# main.net
KiCad netlist of a schematic drawn in Altium Designer
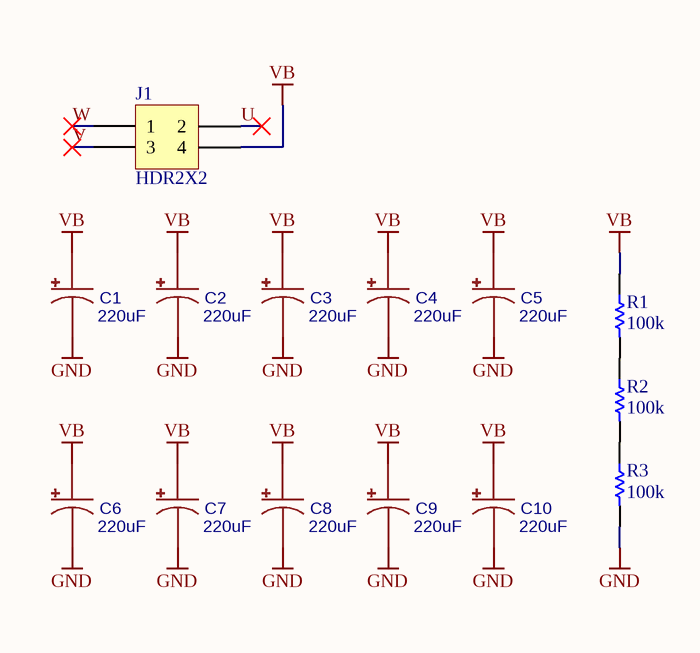
[diagram p0: main.SchDoc]

(export (version "E")
  (design (tool "Eeschema 10.0.6"))
  (components
    (comp (ref "C1")
      (value "220uF")
      (footprint "CAP-TH_BD16.0-P7.50-D1.2-FD")
      (description "UPW2A221MHD")
      (libsource (lib "altium-import") (part "root_0_220uF_"))
    )
    (comp (ref "C2")
      (value "220uF")
      (footprint "CAP-TH_BD16.0-P7.50-D1.2-FD")
      (description "UPW2A221MHD")
      (libsource (lib "altium-import") (part "root_0_220uF_"))
    )
    (comp (ref "C3")
      (value "220uF")
      (footprint "CAP-TH_BD16.0-P7.50-D1.2-FD")
      (description "UPW2A221MHD")
      (libsource (lib "altium-import") (part "root_0_220uF_"))
    )
    (comp (ref "C4")
      (value "220uF")
      (footprint "CAP-TH_BD16.0-P7.50-D1.2-FD")
      (description "UPW2A221MHD")
      (libsource (lib "altium-import") (part "root_0_220uF_"))
    )
    (comp (ref "C5")
      (value "220uF")
      (footprint "CAP-TH_BD16.0-P7.50-D1.2-FD")
      (description "UPW2A221MHD")
      (libsource (lib "altium-import") (part "root_0_220uF_"))
    )
    (comp (ref "C6")
      (value "220uF")
      (footprint "CAP-TH_BD16.0-P7.50-D1.2-FD")
      (description "UPW2A221MHD")
      (libsource (lib "altium-import") (part "root_0_220uF_"))
    )
    (comp (ref "C7")
      (value "220uF")
      (footprint "CAP-TH_BD16.0-P7.50-D1.2-FD")
      (description "UPW2A221MHD")
      (libsource (lib "altium-import") (part "root_0_220uF_"))
    )
    (comp (ref "C8")
      (value "220uF")
      (footprint "CAP-TH_BD16.0-P7.50-D1.2-FD")
      (description "UPW2A221MHD")
      (libsource (lib "altium-import") (part "root_0_220uF_"))
    )
    (comp (ref "C9")
      (value "220uF")
      (footprint "CAP-TH_BD16.0-P7.50-D1.2-FD")
      (description "UPW2A221MHD")
      (libsource (lib "altium-import") (part "root_0_220uF_"))
    )
    (comp (ref "C10")
      (value "220uF")
      (footprint "CAP-TH_BD16.0-P7.50-D1.2-FD")
      (description "UPW2A221MHD")
      (libsource (lib "altium-import") (part "root_0_220uF_"))
    )
    (comp (ref "J1") (value "HDR2X2") (footprint "HDR-2X2") (libsource (lib "Schlib1") (part "Header 2x2")))
    (comp (ref "R1")
      (value "100k")
      (footprint "R0805")
      (description "100k 0805")
      (libsource (lib "Miscellaneous Devices") (part "Res1"))
    )
    (comp (ref "R2")
      (value "100k")
      (footprint "R0805")
      (description "100k 0805")
      (libsource (lib "Miscellaneous Devices") (part "Res1"))
    )
    (comp (ref "R3")
      (value "100k")
      (footprint "R0805")
      (description "100k 0805")
      (libsource (lib "Miscellaneous Devices") (part "Res1"))
    )
  )
  (nets
    (net (code "1") (name "/U") (class "Default")
      (node (ref "J1") (pin "2") (pinfunction "2_2") (pintype "passive+no_connect"))
    )
    (net (code "2") (name "/V") (class "Default")
      (node (ref "J1") (pin "3") (pinfunction "3_3") (pintype "passive+no_connect"))
    )
    (net (code "3") (name "/W") (class "Default")
      (node (ref "J1") (pin "1") (pinfunction "1_1") (pintype "passive+no_connect"))
    )
    (net (code "4") (name "GND") (class "Default")
      (node (ref "C1") (pin "2") (pinfunction "2_2") (pintype "passive"))
      (node (ref "C10") (pin "2") (pinfunction "2_2") (pintype "passive"))
      (node (ref "C2") (pin "2") (pinfunction "2_2") (pintype "passive"))
      (node (ref "C3") (pin "2") (pinfunction "2_2") (pintype "passive"))
      (node (ref "C4") (pin "2") (pinfunction "2_2") (pintype "passive"))
      (node (ref "C5") (pin "2") (pinfunction "2_2") (pintype "passive"))
      (node (ref "C6") (pin "2") (pinfunction "2_2") (pintype "passive"))
      (node (ref "C7") (pin "2") (pinfunction "2_2") (pintype "passive"))
      (node (ref "C8") (pin "2") (pinfunction "2_2") (pintype "passive"))
      (node (ref "C9") (pin "2") (pinfunction "2_2") (pintype "passive"))
      (node (ref "R3") (pin "2") (pinfunction "2_2") (pintype "passive"))
    )
    (net (code "5") (name "Net-(R1-Pad2)") (class "Default")
      (node (ref "R1") (pin "2") (pinfunction "2_2") (pintype "passive"))
      (node (ref "R2") (pin "1") (pinfunction "1_1") (pintype "passive"))
    )
    (net (code "6") (name "Net-(R2-Pad2)") (class "Default")
      (node (ref "R2") (pin "2") (pinfunction "2_2") (pintype "passive"))
      (node (ref "R3") (pin "1") (pinfunction "1_1") (pintype "passive"))
    )
    (net (code "7") (name "VB") (class "Default")
      (node (ref "C1") (pin "1") (pinfunction "1_1") (pintype "passive"))
      (node (ref "C10") (pin "1") (pinfunction "1_1") (pintype "passive"))
      (node (ref "C2") (pin "1") (pinfunction "1_1") (pintype "passive"))
      (node (ref "C3") (pin "1") (pinfunction "1_1") (pintype "passive"))
      (node (ref "C4") (pin "1") (pinfunction "1_1") (pintype "passive"))
      (node (ref "C5") (pin "1") (pinfunction "1_1") (pintype "passive"))
      (node (ref "C6") (pin "1") (pinfunction "1_1") (pintype "passive"))
      (node (ref "C7") (pin "1") (pinfunction "1_1") (pintype "passive"))
      (node (ref "C8") (pin "1") (pinfunction "1_1") (pintype "passive"))
      (node (ref "C9") (pin "1") (pinfunction "1_1") (pintype "passive"))
      (node (ref "J1") (pin "4") (pinfunction "4_4") (pintype "passive"))
      (node (ref "R1") (pin "1") (pinfunction "1_1") (pintype "passive"))
    )
  )
)
